# Encoder_Fin_-_Quadrature_Channel.net
KiCad netlist of a schematic drawn in Altium Designer
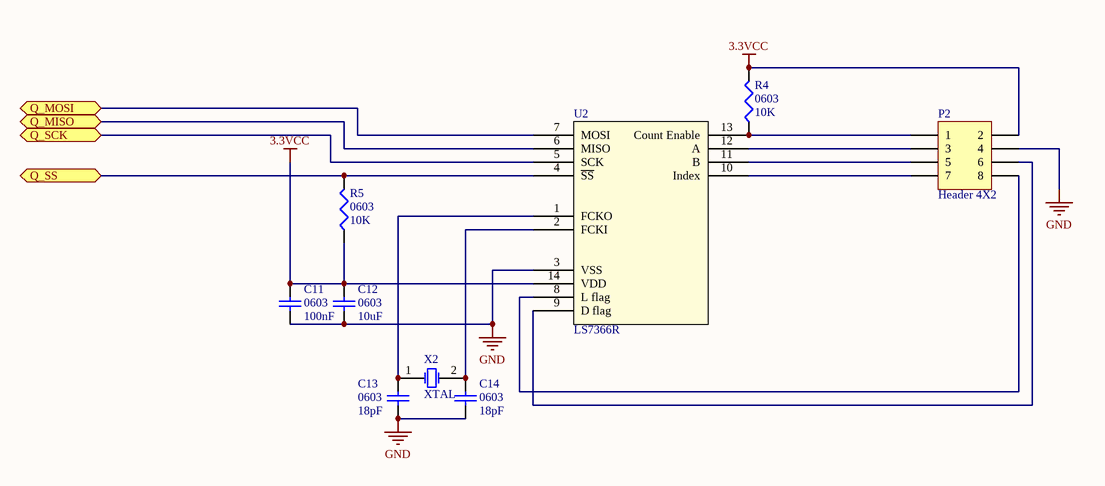
[diagram p0: Encoder Fin - Quadrature  Channel.SchDoc]

(export (version "E")
  (design (tool "Eeschema 10.0.6"))
  (components
    (comp (ref "C11")
      (value "0603")
      (footprint "1608[0603]")
      (description "Capacitor (Semiconductor SIM Model)")
      (fields (field (name "ALTIUM_VALUE") "100nF") (field (name "PUBLISHER") "Altium Limited"))
      (libsource (lib "Miscellaneous Devices") (part "Cap Semi"))
    )
    (comp (ref "C12")
      (value "0603")
      (footprint "1608[0603]")
      (description "Capacitor (Semiconductor SIM Model)")
      (fields (field (name "ALTIUM_VALUE") "10uF") (field (name "PUBLISHER") "Altium Limited"))
      (libsource (lib "Miscellaneous Devices") (part "Cap Semi"))
    )
    (comp (ref "C13")
      (value "0603")
      (footprint "1608[0603]")
      (description "Capacitor (Semiconductor SIM Model)")
      (fields (field (name "ALTIUM_VALUE") "18pF") (field (name "PUBLISHER") "Altium Limited"))
      (libsource (lib "Miscellaneous Devices") (part "Cap Semi"))
    )
    (comp (ref "C14")
      (value "0603")
      (footprint "1608[0603]")
      (description "Capacitor (Semiconductor SIM Model)")
      (fields (field (name "ALTIUM_VALUE") "18pF") (field (name "PUBLISHER") "Altium Limited"))
      (libsource (lib "Miscellaneous Devices") (part "Cap Semi"))
    )
    (comp (ref "P2")
      (value "Header 4X2")
      (footprint "HDR2X4")
      (description "Header, 4-Pin, Dual row")
      (fields (field (name "PUBLISHER") "Altium Limited"))
      (libsource (lib "Miscellaneous Connectors") (part "Header 4X2"))
    )
    (comp (ref "R4")
      (value "0603")
      (footprint "J1-0603")
      (description "Resistor")
      (fields (field (name "ALTIUM_VALUE") "10K") (field (name "PUBLISHER") "Altium Limited"))
      (libsource (lib "Miscellaneous Devices") (part "Res3"))
    )
    (comp (ref "R5")
      (value "0603")
      (footprint "J1-0603")
      (description "Resistor")
      (fields (field (name "ALTIUM_VALUE") "10K") (field (name "PUBLISHER") "Altium Limited"))
      (libsource (lib "Miscellaneous Devices") (part "Res3"))
    )
    (comp (ref "U2")
      (value "LS7366R")
      (footprint "SOIC127P630X175-14N")
      (libsource (lib "LS7366R") (part "LS7366R"))
    )
    (comp (ref "X2")
      (value "XTAL")
      (footprint "ABM7-10.0000MHZ-D2Y-T")
      (description "Crystal Oscillator")
      (fields (field (name "PUBLISHER") "Altium Limited"))
      (libsource (lib "Miscellaneous Devices") (part "XTAL"))
    )
  )
  (nets
    (net (code "1") (name "/Q_MISO") (class "Default")
      (node (ref "U2") (pin "6") (pinfunction "MISO_6") (pintype "passive"))
    )
    (net (code "2") (name "/Q_MOSI") (class "Default")
      (node (ref "U2") (pin "7") (pinfunction "MOSI_7") (pintype "passive"))
    )
    (net (code "3") (name "/Q_SCK") (class "Default")
      (node (ref "U2") (pin "5") (pinfunction "SCK_5") (pintype "passive"))
    )
    (net (code "4") (name "/Q_SS") (class "Default")
      (node (ref "R5") (pin "2") (pinfunction "2_2") (pintype "passive"))
      (node (ref "U2") (pin "4") (pinfunction "~{SS}_4") (pintype "passive"))
    )
    (net (code "5") (name "3.3VCC") (class "Default")
      (node (ref "C11") (pin "2") (pinfunction "2_2") (pintype "passive"))
      (node (ref "C12") (pin "2") (pinfunction "2_2") (pintype "passive"))
      (node (ref "P2") (pin "2") (pinfunction "2_2") (pintype "passive"))
      (node (ref "R4") (pin "2") (pinfunction "2_2") (pintype "passive"))
      (node (ref "R5") (pin "1") (pinfunction "1_1") (pintype "passive"))
      (node (ref "U2") (pin "14") (pinfunction "VDD_14") (pintype "passive"))
    )
    (net (code "6") (name "GND") (class "Default")
      (node (ref "C11") (pin "1") (pinfunction "1_1") (pintype "passive"))
      (node (ref "C12") (pin "1") (pinfunction "1_1") (pintype "passive"))
      (node (ref "C13") (pin "1") (pinfunction "1_1") (pintype "passive"))
      (node (ref "C14") (pin "1") (pinfunction "1_1") (pintype "passive"))
      (node (ref "P2") (pin "4") (pinfunction "4_4") (pintype "passive"))
      (node (ref "U2") (pin "3") (pinfunction "VSS_3") (pintype "passive"))
    )
    (net (code "7") (name "Net-(U2-A)") (class "Default")
      (node (ref "P2") (pin "3") (pinfunction "3_3") (pintype "passive"))
      (node (ref "U2") (pin "12") (pinfunction "A_12") (pintype "passive"))
    )
    (net (code "8") (name "Net-(U2-B)") (class "Default")
      (node (ref "P2") (pin "5") (pinfunction "5_5") (pintype "passive"))
      (node (ref "U2") (pin "11") (pinfunction "B_11") (pintype "passive"))
    )
    (net (code "9") (name "Net-(U2-Count_Enable)") (class "Default")
      (node (ref "P2") (pin "1") (pinfunction "1_1") (pintype "passive"))
      (node (ref "R4") (pin "1") (pinfunction "1_1") (pintype "passive"))
      (node (ref "U2") (pin "13") (pinfunction "Count_Enable_13") (pintype "passive"))
    )
    (net (code "10") (name "Net-(U2-D_flag)") (class "Default")
      (node (ref "P2") (pin "6") (pinfunction "6_6") (pintype "passive"))
      (node (ref "U2") (pin "9") (pinfunction "D_flag_9") (pintype "passive"))
    )
    (net (code "11") (name "Net-(U2-FCKI)") (class "Default")
      (node (ref "C14") (pin "2") (pinfunction "2_2") (pintype "passive"))
      (node (ref "U2") (pin "2") (pinfunction "FCKI_2") (pintype "passive"))
      (node (ref "X2") (pin "2") (pinfunction "OSC2_2") (pintype "passive"))
    )
    (net (code "12") (name "Net-(U2-FCKO)") (class "Default")
      (node (ref "C13") (pin "2") (pinfunction "2_2") (pintype "passive"))
      (node (ref "U2") (pin "1") (pinfunction "FCKO_1") (pintype "passive"))
      (node (ref "X2") (pin "1") (pinfunction "OSC1_1") (pintype "passive"))
    )
    (net (code "13") (name "Net-(U2-Index)") (class "Default")
      (node (ref "P2") (pin "7") (pinfunction "7_7") (pintype "passive"))
      (node (ref "U2") (pin "10") (pinfunction "Index_10") (pintype "passive"))
    )
    (net (code "14") (name "Net-(U2-L_flag)") (class "Default")
      (node (ref "P2") (pin "8") (pinfunction "8_8") (pintype "passive"))
      (node (ref "U2") (pin "8") (pinfunction "L_flag_8") (pintype "passive"))
    )
  )
)
